# Smart_Controler_Lolin_D32.net
KiCad netlist of a schematic drawn in EasyEDA
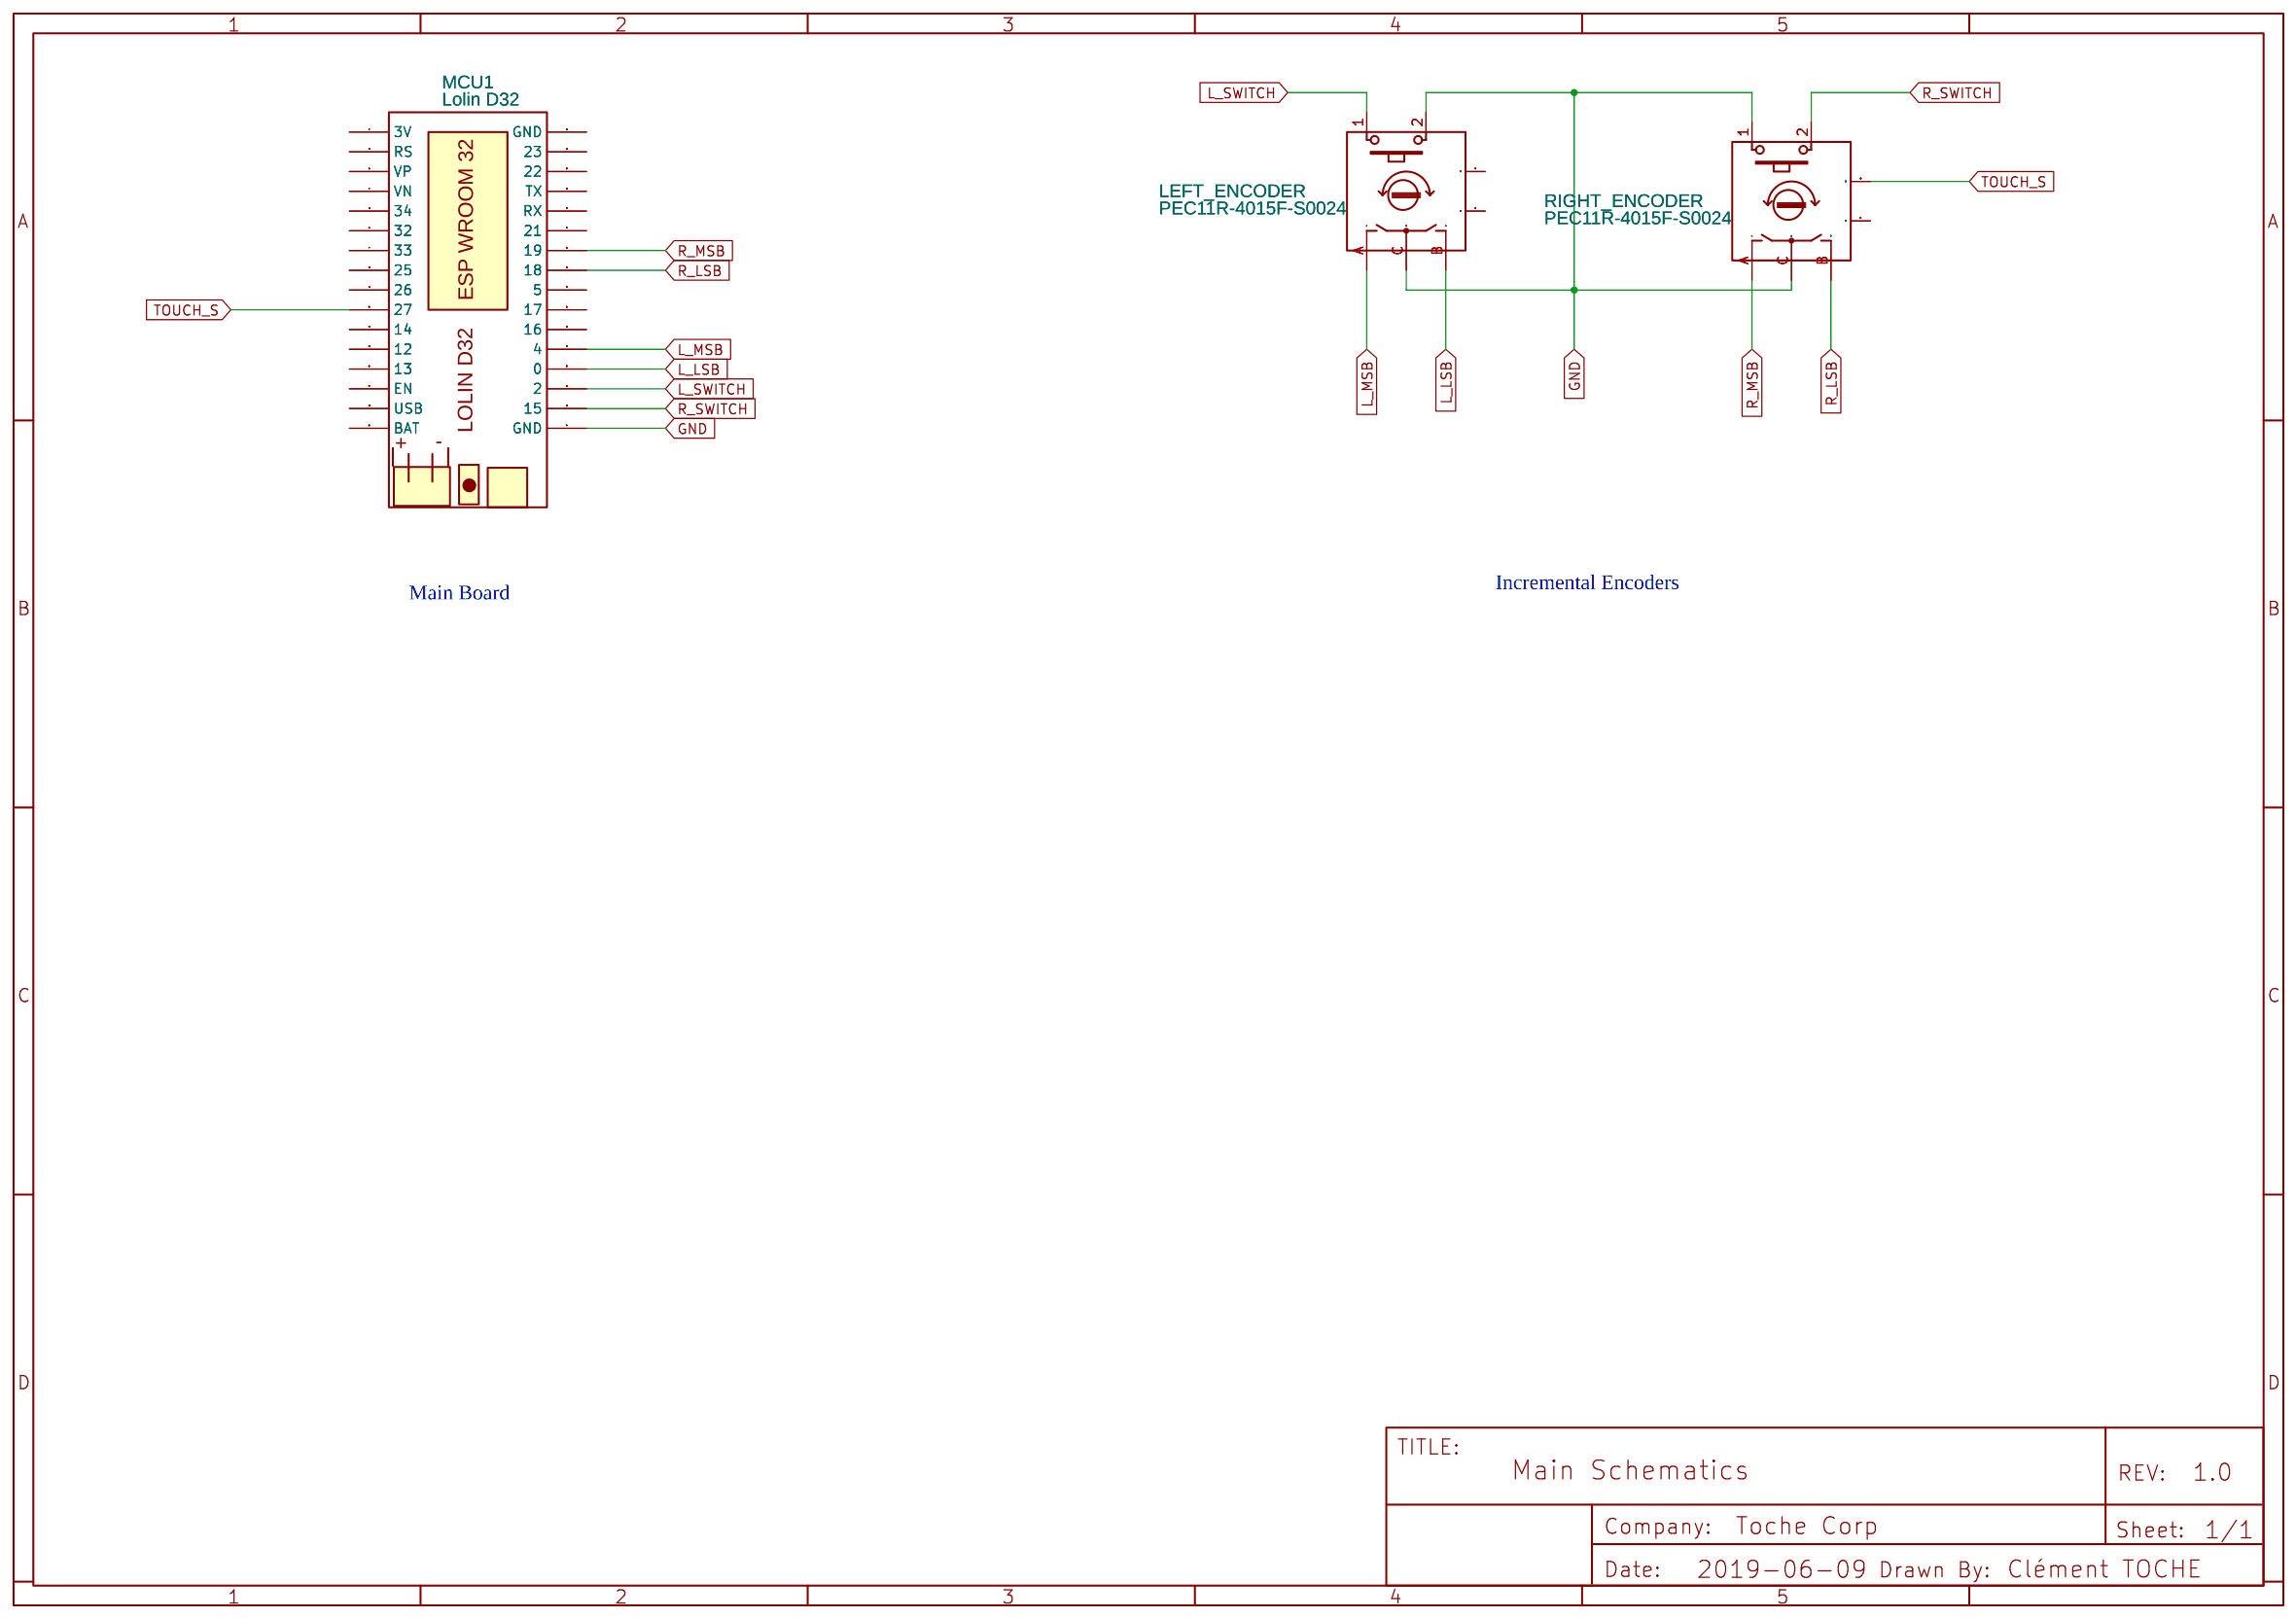
[diagram p0: schematic sheet]

(export (version "E")
  (design (tool "Eeschema 10.0.6"))
  (components
    (comp (ref "LEFT_ENCODER")
      (value "PEC11R-4015F-S0024")
      (fields (field (name "BOM_Supplier Part") "C143789"))
      (libsource (lib "") (part "Unknown_715_90"))
    )
    (comp (ref "MCU1")
      (value "Lolin D32")
      (fields (field (name "BOM_Manufacturer Part") "New SchematicLib"))
      (libsource (lib "") (part "Unknown_230_80"))
    )
    (comp (ref "RIGHT_ENCODER")
      (value "PEC11R-4015F-S0024")
      (fields (field (name "BOM_Supplier Part") "C143789"))
      (libsource (lib "") (part "Unknown_910_95"))
    )
  )
  (nets
    (net (code "1") (name "GND") (class "Default")
      (node (ref "LEFT_ENCODER") (pin "2") (pinfunction "2_2") (pintype "unspecified"))
      (node (ref "LEFT_ENCODER") (pin "C") (pinfunction "C_C") (pintype "unspecified"))
      (node (ref "MCU1") (pin "17") (pinfunction "GND_17") (pintype "unspecified"))
      (node (ref "RIGHT_ENCODER") (pin "1") (pinfunction "1_1") (pintype "unspecified"))
      (node (ref "RIGHT_ENCODER") (pin "C") (pinfunction "C_C") (pintype "unspecified"))
    )
    (net (code "2") (name "L_LSB") (class "Default")
      (node (ref "LEFT_ENCODER") (pin "B") (pinfunction "B_B") (pintype "unspecified"))
      (node (ref "MCU1") (pin "20") (pinfunction "0_20") (pintype "unspecified"))
    )
    (net (code "3") (name "L_MSB") (class "Default")
      (node (ref "LEFT_ENCODER") (pin "A") (pinfunction "A_A") (pintype "unspecified"))
      (node (ref "MCU1") (pin "21") (pinfunction "4_21") (pintype "unspecified"))
    )
    (net (code "4") (name "L_SWITCH") (class "Default")
      (node (ref "LEFT_ENCODER") (pin "1") (pinfunction "1_1") (pintype "unspecified"))
      (node (ref "MCU1") (pin "19") (pinfunction "2_19") (pintype "unspecified"))
    )
    (net (code "5") (name "R_LSB") (class "Default")
      (node (ref "MCU1") (pin "25") (pinfunction "18_25") (pintype "unspecified"))
      (node (ref "RIGHT_ENCODER") (pin "B") (pinfunction "B_B") (pintype "unspecified"))
    )
    (net (code "6") (name "R_MSB") (class "Default")
      (node (ref "MCU1") (pin "26") (pinfunction "19_26") (pintype "unspecified"))
      (node (ref "RIGHT_ENCODER") (pin "A") (pinfunction "A_A") (pintype "unspecified"))
    )
    (net (code "7") (name "R_SWITCH") (class "Default")
      (node (ref "MCU1") (pin "18") (pinfunction "15_18") (pintype "unspecified"))
      (node (ref "RIGHT_ENCODER") (pin "2") (pinfunction "2_2") (pintype "unspecified"))
    )
    (net (code "8") (name "TOUCH_S") (class "Default")
      (node (ref "MCU1") (pin "10") (pinfunction "27_10") (pintype "unspecified"))
      (node (ref "RIGHT_ENCODER") (pin "MT2") (pinfunction "MT2_MT2") (pintype "unspecified"))
    )
    (net (code "9") (name "unconnected-(LEFT_ENCODER-PadMT1)") (class "Default")
      (node (ref "LEFT_ENCODER") (pin "MT1") (pinfunction "MT1_MT1") (pintype "unspecified"))
    )
    (net (code "10") (name "unconnected-(LEFT_ENCODER-PadMT2)") (class "Default")
      (node (ref "LEFT_ENCODER") (pin "MT2") (pinfunction "MT2_MT2") (pintype "unspecified"))
    )
    (net (code "11") (name "unconnected-(MCU1-3V-Pad1)") (class "Default")
      (node (ref "MCU1") (pin "1") (pinfunction "3V_1") (pintype "unspecified"))
    )
    (net (code "12") (name "unconnected-(MCU1-5-Pad24)") (class "Default")
      (node (ref "MCU1") (pin "24") (pinfunction "5_24") (pintype "unspecified"))
    )
    (net (code "13") (name "unconnected-(MCU1-14-Pad11)") (class "Default")
      (node (ref "MCU1") (pin "11") (pinfunction "14_11") (pintype "unspecified"))
    )
    (net (code "14") (name "unconnected-(MCU1-16-Pad22)") (class "Default")
      (node (ref "MCU1") (pin "22") (pinfunction "16_22") (pintype "unspecified"))
    )
    (net (code "15") (name "unconnected-(MCU1-17-Pad23)") (class "Default")
      (node (ref "MCU1") (pin "23") (pinfunction "17_23") (pintype "unspecified"))
    )
    (net (code "16") (name "unconnected-(MCU1-21-Pad27)") (class "Default")
      (node (ref "MCU1") (pin "27") (pinfunction "21_27") (pintype "unspecified"))
    )
    (net (code "17") (name "unconnected-(MCU1-22-Pad30)") (class "Default")
      (node (ref "MCU1") (pin "30") (pinfunction "22_30") (pintype "unspecified"))
    )
    (net (code "18") (name "unconnected-(MCU1-23-Pad31)") (class "Default")
      (node (ref "MCU1") (pin "31") (pinfunction "23_31") (pintype "unspecified"))
    )
    (net (code "19") (name "unconnected-(MCU1-25-Pad8)") (class "Default")
      (node (ref "MCU1") (pin "8") (pinfunction "25_8") (pintype "unspecified"))
    )
    (net (code "20") (name "unconnected-(MCU1-26-Pad9)") (class "Default")
      (node (ref "MCU1") (pin "9") (pinfunction "26_9") (pintype "unspecified"))
    )
    (net (code "21") (name "unconnected-(MCU1-32-Pad6)") (class "Default")
      (node (ref "MCU1") (pin "6") (pinfunction "32_6") (pintype "unspecified"))
    )
    (net (code "22") (name "unconnected-(MCU1-33-Pad7)") (class "Default")
      (node (ref "MCU1") (pin "7") (pinfunction "33_7") (pintype "unspecified"))
    )
    (net (code "23") (name "unconnected-(MCU1-34-Pad5)") (class "Default")
      (node (ref "MCU1") (pin "5") (pinfunction "34_5") (pintype "unspecified"))
    )
    (net (code "24") (name "unconnected-(MCU1-BAT-Pad16)") (class "Default")
      (node (ref "MCU1") (pin "16") (pinfunction "BAT_16") (pintype "unspecified"))
    )
    (net (code "25") (name "unconnected-(MCU1-EN-Pad14)") (class "Default")
      (node (ref "MCU1") (pin "14") (pinfunction "EN_14") (pintype "unspecified"))
    )
    (net (code "26") (name "unconnected-(MCU1-GND-Pad32)") (class "Default")
      (node (ref "MCU1") (pin "32") (pinfunction "GND_32") (pintype "unspecified"))
    )
    (net (code "27") (name "unconnected-(MCU1-Pad12)") (class "Default")
      (node (ref "MCU1") (pin "12") (pinfunction "12_12") (pintype "unspecified"))
    )
    (net (code "28") (name "unconnected-(MCU1-Pad13)") (class "Default")
      (node (ref "MCU1") (pin "13") (pinfunction "13_13") (pintype "unspecified"))
    )
    (net (code "29") (name "unconnected-(MCU1-RS-Pad2)") (class "Default")
      (node (ref "MCU1") (pin "2") (pinfunction "RS_2") (pintype "unspecified"))
    )
    (net (code "30") (name "unconnected-(MCU1-RX-Pad28)") (class "Default")
      (node (ref "MCU1") (pin "28") (pinfunction "RX_28") (pintype "unspecified"))
    )
    (net (code "31") (name "unconnected-(MCU1-TX-Pad29)") (class "Default")
      (node (ref "MCU1") (pin "29") (pinfunction "TX_29") (pintype "unspecified"))
    )
    (net (code "32") (name "unconnected-(MCU1-USB-Pad15)") (class "Default")
      (node (ref "MCU1") (pin "15") (pinfunction "USB_15") (pintype "unspecified"))
    )
    (net (code "33") (name "unconnected-(MCU1-VN-Pad4)") (class "Default")
      (node (ref "MCU1") (pin "4") (pinfunction "VN_4") (pintype "unspecified"))
    )
    (net (code "34") (name "unconnected-(MCU1-VP-Pad3)") (class "Default")
      (node (ref "MCU1") (pin "3") (pinfunction "VP_3") (pintype "unspecified"))
    )
    (net (code "35") (name "unconnected-(RIGHT_ENCODER-PadMT1)") (class "Default")
      (node (ref "RIGHT_ENCODER") (pin "MT1") (pinfunction "MT1_MT1") (pintype "unspecified"))
    )
  )
)
